# headamp.net
KiCad netlist of a schematic drawn in EAGLE
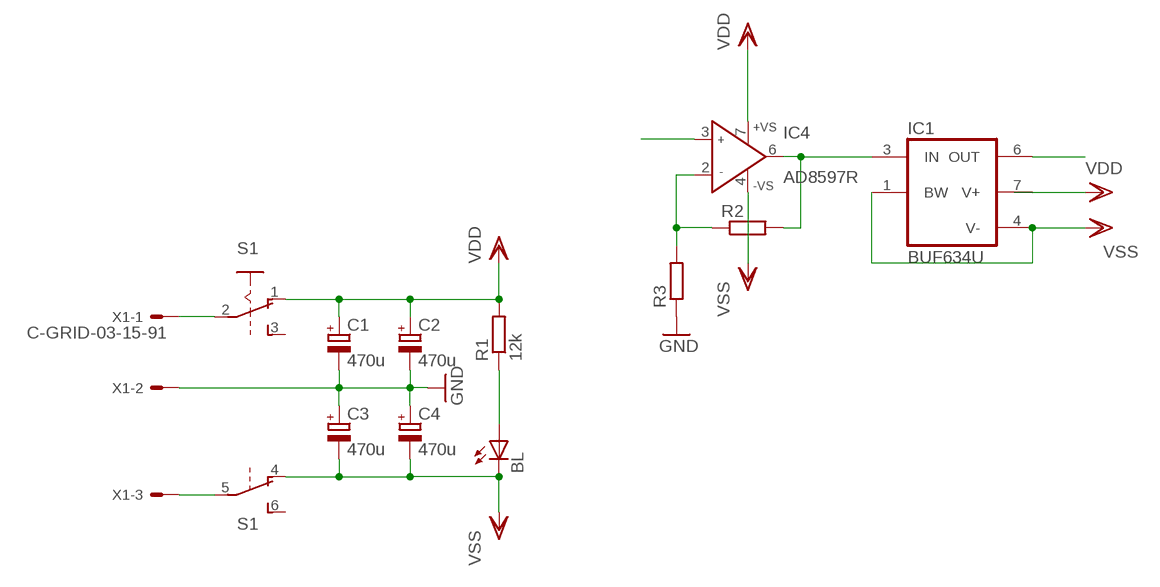
[diagram p0: schematic, sheet 1]

(export (version "E")
  (design (tool "Eeschema 10.0.6"))
  (components
    (comp (ref "BL")
      (value "LEDCHIPLED_0805")
      (footprint "eagle-import:CHIPLED_0805")
      (libsource (lib "eagle-import") (part "LEDCHIPLED_0805"))
    )
    (comp (ref "C1")
      (value "470u")
      (footprint "eagle-import:PANASONIC_C")
      (libsource (lib "eagle-import") (part "CPOL-EUC"))
    )
    (comp (ref "C2")
      (value "470u")
      (footprint "eagle-import:PANASONIC_C")
      (libsource (lib "eagle-import") (part "CPOL-EUC"))
    )
    (comp (ref "C3")
      (value "470u")
      (footprint "eagle-import:PANASONIC_C")
      (libsource (lib "eagle-import") (part "CPOL-EUC"))
    )
    (comp (ref "C4")
      (value "470u")
      (footprint "eagle-import:PANASONIC_C")
      (libsource (lib "eagle-import") (part "CPOL-EUC"))
    )
    (comp (ref "IC1")
      (value "BUF634U")
      (footprint "eagle-import:SO08")
      (fields (field (name "MF") "TEXAS INSTRUMENTS"))
      (libsource (lib "eagle-import") (part "BUF634U"))
    )
    (comp (ref "IC4")
      (value "AD8597R")
      (footprint "eagle-import:SO8")
      (fields (field (name "MPN") "AD8597ARZ"))
      (libsource (lib "eagle-import") (part "AD8597R"))
    )
    (comp (ref "R1")
      (value "12k")
      (footprint "eagle-import:R0805")
      (libsource (lib "eagle-import") (part "R-EU_R0805"))
    )
    (comp (ref "R2")
      (value "R-EU_R1206")
      (footprint "eagle-import:R1206")
      (libsource (lib "eagle-import") (part "R-EU_R1206"))
    )
    (comp (ref "R3")
      (value "R-EU_R1206")
      (footprint "eagle-import:R1206")
      (libsource (lib "eagle-import") (part "R-EU_R1206"))
    )
    (comp (ref "S1")
      (value "A68-A31")
      (footprint "eagle-import:A68-A31")
      (libsource (lib "eagle-import") (part "A68-A31"))
    )
    (comp (ref "X1")
      (value "C-GRID-03-15-91")
      (footprint "eagle-import:15-91-03")
      (libsource (lib "eagle-import") (part "C-GRID-03-15-91"))
    )
  )
  (nets
    (net (code "1") (name "/V+") (class "Default")
      (node (ref "IC1") (pin "7") (pinfunction "V+_7") (pintype "power_in"))
    )
    (net (code "2") (name "GND") (class "Default")
      (node (ref "C1") (pin "-") (pinfunction "-_-") (pintype "passive"))
      (node (ref "C2") (pin "-") (pinfunction "-_-") (pintype "passive"))
      (node (ref "C3") (pin "+") (pinfunction "+_+") (pintype "passive"))
      (node (ref "C4") (pin "+") (pinfunction "+_+") (pintype "passive"))
      (node (ref "R3") (pin "1") (pinfunction "1_1") (pintype "passive"))
      (node (ref "X1") (pin "2") (pinfunction "S_2") (pintype "passive"))
    )
    (net (code "3") (name "Net-(BL-PadA)") (class "Default")
      (node (ref "BL") (pin "A") (pinfunction "A_A") (pintype "passive"))
      (node (ref "R1") (pin "1") (pinfunction "1_1") (pintype "passive"))
    )
    (net (code "4") (name "Net-(IC1-IN)") (class "Default")
      (node (ref "IC1") (pin "3") (pinfunction "IN_3") (pintype "input"))
      (node (ref "IC4") (pin "6") (pinfunction "OUT_6") (pintype "output"))
      (node (ref "R2") (pin "2") (pinfunction "2_2") (pintype "passive"))
    )
    (net (code "5") (name "Net-(IC4-IN-)") (class "Default")
      (node (ref "IC4") (pin "2") (pinfunction "IN-_2") (pintype "input"))
      (node (ref "R2") (pin "1") (pinfunction "1_1") (pintype "passive"))
      (node (ref "R3") (pin "2") (pinfunction "2_2") (pintype "passive"))
    )
    (net (code "6") (name "Net-(S1A-P)") (class "Default")
      (node (ref "S1") (pin "2") (pinfunction "P_2") (pintype "passive"))
      (node (ref "X1") (pin "1") (pinfunction "S_1") (pintype "passive"))
    )
    (net (code "7") (name "Net-(S1B-P)") (class "Default")
      (node (ref "S1") (pin "5") (pinfunction "P_5") (pintype "passive"))
      (node (ref "X1") (pin "3") (pinfunction "S_3") (pintype "passive"))
    )
    (net (code "8") (name "VDD") (class "Default")
      (node (ref "C1") (pin "+") (pinfunction "+_+") (pintype "passive"))
      (node (ref "C2") (pin "+") (pinfunction "+_+") (pintype "passive"))
      (node (ref "IC4") (pin "7") (pinfunction "+VS_7") (pintype "input"))
      (node (ref "R1") (pin "2") (pinfunction "2_2") (pintype "passive"))
      (node (ref "S1") (pin "1") (pinfunction "O_1") (pintype "passive"))
    )
    (net (code "9") (name "VSS") (class "Default")
      (node (ref "BL") (pin "C") (pinfunction "C_C") (pintype "passive"))
      (node (ref "C3") (pin "-") (pinfunction "-_-") (pintype "passive"))
      (node (ref "C4") (pin "-") (pinfunction "-_-") (pintype "passive"))
      (node (ref "IC1") (pin "1") (pinfunction "BW_1") (pintype "passive"))
      (node (ref "IC1") (pin "4") (pinfunction "V-_4") (pintype "power_in"))
      (node (ref "IC4") (pin "4") (pinfunction "-VS_4") (pintype "input"))
      (node (ref "S1") (pin "4") (pinfunction "O_4") (pintype "passive"))
    )
    (net (code "10") (name "unconnected-(IC1-OUT-Pad6)") (class "Default")
      (node (ref "IC1") (pin "6") (pinfunction "OUT_6") (pintype "output"))
    )
    (net (code "11") (name "unconnected-(IC4-IN+-Pad3)") (class "Default")
      (node (ref "IC4") (pin "3") (pinfunction "IN+_3") (pintype "input"))
    )
    (net (code "12") (name "unconnected-(S1A-S-Pad3)") (class "Default")
      (node (ref "S1") (pin "3") (pinfunction "S_3") (pintype "passive"))
    )
    (net (code "13") (name "unconnected-(S1B-S-Pad6)") (class "Default")
      (node (ref "S1") (pin "6") (pinfunction "S_6") (pintype "passive"))
    )
  )
)
